# SUBA.net
KiCad netlist of a schematic drawn in EAGLE
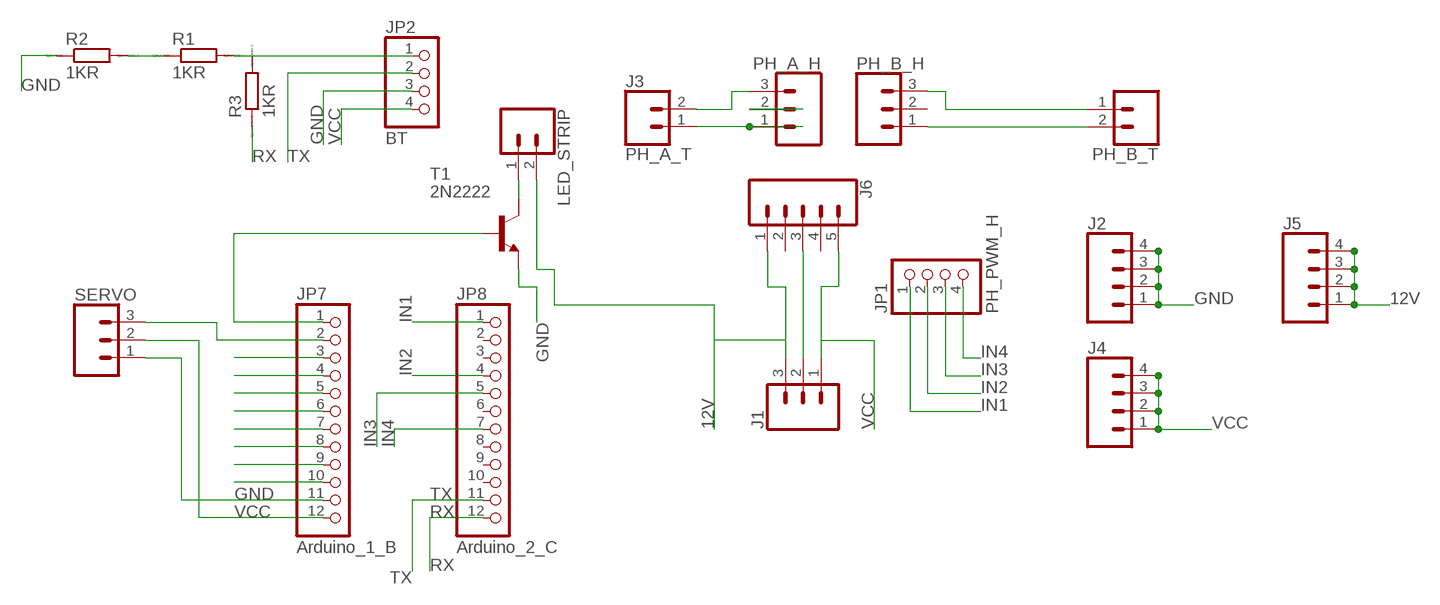
[diagram p0: schematic, sheet 1]

(export (version "E")
  (design (tool "Eeschema 10.0.6"))
  (components
    (comp (ref "J1")
      (value "CONN_03-SCREW-5MM")
      (footprint "eagle-import:SCREWTERMINAL-5MM-3")
      (libsource (lib "eagle-import") (part "CONN_03-SCREW-5MM"))
    )
    (comp (ref "J2")
      (value "CONN_04")
      (footprint "eagle-import:1X04")
      (libsource (lib "eagle-import") (part "CONN_04"))
    )
    (comp (ref "J3")
      (value "PH_A_T")
      (footprint "eagle-import:SCREWTERMINAL-5MM-2")
      (libsource (lib "eagle-import") (part "CONN_025MM"))
    )
    (comp (ref "J4")
      (value "CONN_04")
      (footprint "eagle-import:1X04")
      (libsource (lib "eagle-import") (part "CONN_04"))
    )
    (comp (ref "J5")
      (value "CONN_04")
      (footprint "eagle-import:1X04")
      (libsource (lib "eagle-import") (part "CONN_04"))
    )
    (comp (ref "J6")
      (value "CONN_05")
      (footprint "eagle-import:1X05")
      (libsource (lib "eagle-import") (part "CONN_05"))
    )
    (comp (ref "JP1")
      (value "PH_PWM_H")
      (footprint "eagle-import:1X04")
      (libsource (lib "eagle-import") (part "PINHD-1X4"))
    )
    (comp (ref "JP2")
      (value "BT")
      (footprint "eagle-import:1X04")
      (libsource (lib "eagle-import") (part "PINHD-1X4"))
    )
    (comp (ref "JP7")
      (value "Arduino_1_B")
      (footprint "eagle-import:1X12")
      (libsource (lib "eagle-import") (part "PINHD-1X12"))
    )
    (comp (ref "JP8")
      (value "Arduino_2_C")
      (footprint "eagle-import:1X12")
      (libsource (lib "eagle-import") (part "PINHD-1X12"))
    )
    (comp (ref "LED_STRIP")
      (value "CONN_02")
      (footprint "eagle-import:1X02")
      (libsource (lib "eagle-import") (part "CONN_02"))
    )
    (comp (ref "PH_A_H")
      (value "CONN_03")
      (footprint "eagle-import:1X03")
      (libsource (lib "eagle-import") (part "CONN_03"))
    )
    (comp (ref "PH_B_H")
      (value "CONN_03")
      (footprint "eagle-import:1X03")
      (libsource (lib "eagle-import") (part "CONN_03"))
    )
    (comp (ref "PH_B_T")
      (value "CONN_025MM")
      (footprint "eagle-import:SCREWTERMINAL-5MM-2")
      (libsource (lib "eagle-import") (part "CONN_025MM"))
    )
    (comp (ref "R1")
      (value "1KR")
      (footprint "eagle-import:0204_7")
      (libsource (lib "eagle-import") (part "R0204/7"))
    )
    (comp (ref "R2")
      (value "1KR")
      (footprint "eagle-import:0204_7")
      (libsource (lib "eagle-import") (part "R0204/7"))
    )
    (comp (ref "R3")
      (value "1KR")
      (footprint "eagle-import:0204_7")
      (libsource (lib "eagle-import") (part "R0204/7"))
    )
    (comp (ref "SERVO")
      (value "CONN_03")
      (footprint "eagle-import:1X03")
      (libsource (lib "eagle-import") (part "CONN_03"))
    )
    (comp (ref "T1")
      (value "2N2222")
      (footprint "eagle-import:TO92-EBC-OVAL")
      (libsource (lib "eagle-import") (part "2N2222"))
    )
  )
  (nets
    (net (code "1") (name "/12V") (class "Default")
      (node (ref "J1") (pin "3") (pinfunction "3_3") (pintype "passive"))
      (node (ref "J5") (pin "1") (pinfunction "1_1") (pintype "passive"))
      (node (ref "J5") (pin "2") (pinfunction "2_2") (pintype "passive"))
      (node (ref "J5") (pin "3") (pinfunction "3_3") (pintype "passive"))
      (node (ref "J5") (pin "4") (pinfunction "4_4") (pintype "passive"))
      (node (ref "J6") (pin "1") (pinfunction "1_1") (pintype "passive"))
      (node (ref "LED_STRIP") (pin "2") (pinfunction "2_2") (pintype "passive"))
    )
    (net (code "2") (name "/GND") (class "Default")
      (node (ref "J1") (pin "2") (pinfunction "2_2") (pintype "passive"))
      (node (ref "J2") (pin "1") (pinfunction "1_1") (pintype "passive"))
      (node (ref "J2") (pin "2") (pinfunction "2_2") (pintype "passive"))
      (node (ref "J2") (pin "3") (pinfunction "3_3") (pintype "passive"))
      (node (ref "J2") (pin "4") (pinfunction "4_4") (pintype "passive"))
      (node (ref "J6") (pin "3") (pinfunction "3_3") (pintype "passive"))
      (node (ref "JP2") (pin "3") (pinfunction "3_3") (pintype "passive"))
      (node (ref "JP7") (pin "11") (pinfunction "11_11") (pintype "passive"))
      (node (ref "R2") (pin "1") (pinfunction "1_1") (pintype "passive"))
      (node (ref "SERVO") (pin "1") (pinfunction "1_1") (pintype "passive"))
      (node (ref "T1") (pin "E") (pinfunction "E_E") (pintype "passive"))
    )
    (net (code "3") (name "/IN1") (class "Default")
      (node (ref "JP1") (pin "1") (pinfunction "1_1") (pintype "passive"))
      (node (ref "JP8") (pin "1") (pinfunction "1_1") (pintype "passive"))
    )
    (net (code "4") (name "/IN2") (class "Default")
      (node (ref "JP1") (pin "2") (pinfunction "2_2") (pintype "passive"))
      (node (ref "JP8") (pin "4") (pinfunction "4_4") (pintype "passive"))
    )
    (net (code "5") (name "/IN3") (class "Default")
      (node (ref "JP1") (pin "3") (pinfunction "3_3") (pintype "passive"))
      (node (ref "JP8") (pin "5") (pinfunction "5_5") (pintype "passive"))
    )
    (net (code "6") (name "/IN4") (class "Default")
      (node (ref "JP1") (pin "4") (pinfunction "4_4") (pintype "passive"))
      (node (ref "JP8") (pin "7") (pinfunction "7_7") (pintype "passive"))
    )
    (net (code "7") (name "/RX") (class "Default")
      (node (ref "JP8") (pin "12") (pinfunction "12_12") (pintype "passive"))
      (node (ref "R3") (pin "1") (pinfunction "1_1") (pintype "passive"))
    )
    (net (code "8") (name "/TX") (class "Default")
      (node (ref "JP2") (pin "2") (pinfunction "2_2") (pintype "passive"))
      (node (ref "JP8") (pin "11") (pinfunction "11_11") (pintype "passive"))
    )
    (net (code "9") (name "/VCC") (class "Default")
      (node (ref "J1") (pin "1") (pinfunction "1_1") (pintype "passive"))
      (node (ref "J4") (pin "1") (pinfunction "1_1") (pintype "passive"))
      (node (ref "J4") (pin "2") (pinfunction "2_2") (pintype "passive"))
      (node (ref "J4") (pin "3") (pinfunction "3_3") (pintype "passive"))
      (node (ref "J4") (pin "4") (pinfunction "4_4") (pintype "passive"))
      (node (ref "J6") (pin "5") (pinfunction "5_5") (pintype "passive"))
      (node (ref "JP2") (pin "4") (pinfunction "4_4") (pintype "passive"))
      (node (ref "JP7") (pin "12") (pinfunction "12_12") (pintype "passive"))
      (node (ref "JP7") (pin "9") (pinfunction "9_9") (pintype "passive"))
      (node (ref "SERVO") (pin "2") (pinfunction "2_2") (pintype "passive"))
    )
    (net (code "10") (name "Net-(J3-Pad1)") (class "Default")
      (node (ref "J3") (pin "1") (pinfunction "1_1") (pintype "passive"))
      (node (ref "PH_A_H") (pin "1") (pinfunction "1_1") (pintype "passive"))
    )
    (net (code "11") (name "Net-(J3-Pad2)") (class "Default")
      (node (ref "J3") (pin "2") (pinfunction "2_2") (pintype "passive"))
      (node (ref "PH_A_H") (pin "3") (pinfunction "3_3") (pintype "passive"))
    )
    (net (code "12") (name "Net-(JP2-Pad1)") (class "Default")
      (node (ref "JP2") (pin "1") (pinfunction "1_1") (pintype "passive"))
      (node (ref "R1") (pin "2") (pinfunction "2_2") (pintype "passive"))
      (node (ref "R3") (pin "2") (pinfunction "2_2") (pintype "passive"))
    )
    (net (code "13") (name "Net-(JP7-Pad1)") (class "Default")
      (node (ref "JP7") (pin "1") (pinfunction "1_1") (pintype "passive"))
      (node (ref "T1") (pin "B") (pinfunction "B_B") (pintype "passive"))
    )
    (net (code "14") (name "Net-(JP7-Pad2)") (class "Default")
      (node (ref "JP7") (pin "2") (pinfunction "2_2") (pintype "passive"))
      (node (ref "SERVO") (pin "3") (pinfunction "3_3") (pintype "passive"))
    )
    (net (code "15") (name "Net-(LED_STRIP-Pad1)") (class "Default")
      (node (ref "LED_STRIP") (pin "1") (pinfunction "1_1") (pintype "passive"))
      (node (ref "T1") (pin "C") (pinfunction "C_C") (pintype "passive"))
    )
    (net (code "16") (name "Net-(PH_B_H-Pad1)") (class "Default")
      (node (ref "PH_B_H") (pin "1") (pinfunction "1_1") (pintype "passive"))
      (node (ref "PH_B_T") (pin "2") (pinfunction "2_2") (pintype "passive"))
    )
    (net (code "17") (name "Net-(PH_B_H-Pad3)") (class "Default")
      (node (ref "PH_B_H") (pin "3") (pinfunction "3_3") (pintype "passive"))
      (node (ref "PH_B_T") (pin "1") (pinfunction "1_1") (pintype "passive"))
    )
    (net (code "18") (name "Net-(R1-Pad1)") (class "Default")
      (node (ref "R1") (pin "1") (pinfunction "1_1") (pintype "passive"))
      (node (ref "R2") (pin "2") (pinfunction "2_2") (pintype "passive"))
    )
    (net (code "19") (name "unconnected-(J6-Pad2)") (class "Default")
      (node (ref "J6") (pin "2") (pinfunction "2_2") (pintype "passive"))
    )
    (net (code "20") (name "unconnected-(J6-Pad4)") (class "Default")
      (node (ref "J6") (pin "4") (pinfunction "4_4") (pintype "passive"))
    )
    (net (code "21") (name "unconnected-(JP7-Pad3)") (class "Default")
      (node (ref "JP7") (pin "3") (pinfunction "3_3") (pintype "passive"))
    )
    (net (code "22") (name "unconnected-(JP7-Pad4)") (class "Default")
      (node (ref "JP7") (pin "4") (pinfunction "4_4") (pintype "passive"))
    )
    (net (code "23") (name "unconnected-(JP7-Pad5)") (class "Default")
      (node (ref "JP7") (pin "5") (pinfunction "5_5") (pintype "passive"))
    )
    (net (code "24") (name "unconnected-(JP7-Pad6)") (class "Default")
      (node (ref "JP7") (pin "6") (pinfunction "6_6") (pintype "passive"))
    )
    (net (code "25") (name "unconnected-(JP7-Pad7)") (class "Default")
      (node (ref "JP7") (pin "7") (pinfunction "7_7") (pintype "passive"))
    )
    (net (code "26") (name "unconnected-(JP7-Pad8)") (class "Default")
      (node (ref "JP7") (pin "8") (pinfunction "8_8") (pintype "passive"))
    )
    (net (code "27") (name "unconnected-(JP7-Pad10)") (class "Default")
      (node (ref "JP7") (pin "10") (pinfunction "10_10") (pintype "passive"))
    )
    (net (code "28") (name "unconnected-(JP8-Pad2)") (class "Default")
      (node (ref "JP8") (pin "2") (pinfunction "2_2") (pintype "passive"))
    )
    (net (code "29") (name "unconnected-(JP8-Pad3)") (class "Default")
      (node (ref "JP8") (pin "3") (pinfunction "3_3") (pintype "passive"))
    )
    (net (code "30") (name "unconnected-(JP8-Pad6)") (class "Default")
      (node (ref "JP8") (pin "6") (pinfunction "6_6") (pintype "passive"))
    )
    (net (code "31") (name "unconnected-(JP8-Pad8)") (class "Default")
      (node (ref "JP8") (pin "8") (pinfunction "8_8") (pintype "passive"))
    )
    (net (code "32") (name "unconnected-(JP8-Pad9)") (class "Default")
      (node (ref "JP8") (pin "9") (pinfunction "9_9") (pintype "passive"))
    )
    (net (code "33") (name "unconnected-(JP8-Pad10)") (class "Default")
      (node (ref "JP8") (pin "10") (pinfunction "10_10") (pintype "passive"))
    )
    (net (code "34") (name "unconnected-(PH_A_H-Pad2)") (class "Default")
      (node (ref "PH_A_H") (pin "2") (pinfunction "2_2") (pintype "passive"))
    )
    (net (code "35") (name "unconnected-(PH_B_H-Pad2)") (class "Default")
      (node (ref "PH_B_H") (pin "2") (pinfunction "2_2") (pintype "passive"))
    )
  )
)
